# Power.net
KiCad netlist of a schematic drawn in Altium Designer
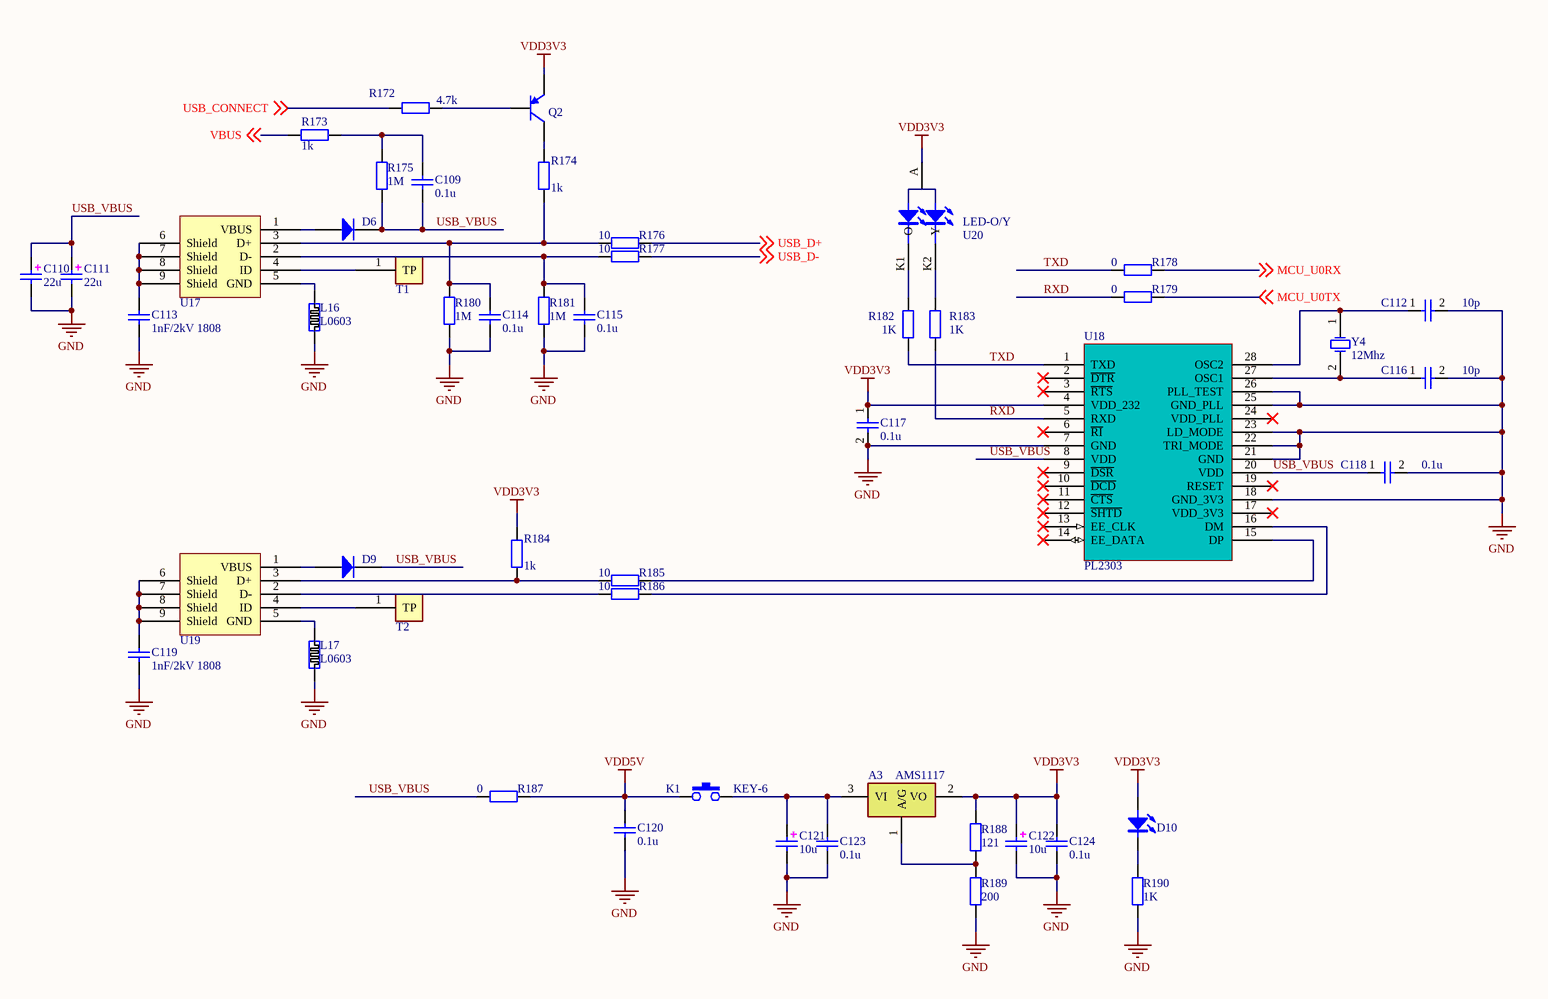
[diagram p0: Power.SchDoc]

(export (version "E")
  (design (tool "Eeschema 10.0.6"))
  (components
    (comp (ref "A3")
      (value "AMS1117")
      (footprint "ASM1117-A")
      (description "1117 LDO")
      (libsource (lib "lpc2368") (part "AMS1117"))
    )
    (comp (ref "C109")
      (value "0.1u")
      (footprint "C0603")
      (description "0603 Capacitor without Polarity")
      (libsource (lib "lpc2368") (part "CAP0603"))
    )
    (comp (ref "C110")
      (value "22u")
      (footprint "C1210")
      (description "钽电容1210封装")
      (libsource (lib "lpc2368") (part "DCAP"))
    )
    (comp (ref "C111")
      (value "22u")
      (footprint "C1210")
      (description "钽电容1210封装")
      (libsource (lib "lpc2368") (part "DCAP"))
    )
    (comp (ref "C112") (value "10p") (footprint "C0603") (libsource (lib "MSP430-LQFP64") (part "cap0603")))
    (comp (ref "C113")
      (value "1nF/2kV 1808")
      (footprint "C1808")
      (description "0603 Capacitor without Polarity")
      (libsource (lib "lpc2368") (part "CAP0603"))
    )
    (comp (ref "C114")
      (value "0.1u")
      (footprint "C0603")
      (description "0603 Capacitor without Polarity")
      (libsource (lib "lpc2368") (part "CAP0603"))
    )
    (comp (ref "C115")
      (value "0.1u")
      (footprint "C0603")
      (description "0603 Capacitor without Polarity")
      (libsource (lib "lpc2368") (part "CAP0603"))
    )
    (comp (ref "C116") (value "10p") (footprint "C0603") (libsource (lib "MSP430-LQFP64") (part "cap0603")))
    (comp (ref "C117") (value "0.1u") (footprint "C0603") (libsource (lib "MSP430-LQFP64") (part "cap0603")))
    (comp (ref "C118") (value "0.1u") (footprint "C0603") (libsource (lib "MSP430-LQFP64") (part "cap0603")))
    (comp (ref "C119")
      (value "1nF/2kV 1808")
      (footprint "C1808")
      (description "0603 Capacitor without Polarity")
      (libsource (lib "lpc2368") (part "CAP0603"))
    )
    (comp (ref "C120")
      (value "0.1u")
      (footprint "C0603")
      (description "0603 Capacitor without Polarity")
      (libsource (lib "lpc2368") (part "CAP0603"))
    )
    (comp (ref "C121")
      (value "10u")
      (footprint "C1210")
      (description "钽电容1210封装")
      (libsource (lib "lpc2368") (part "DCAP"))
    )
    (comp (ref "C122")
      (value "10u")
      (footprint "C1210")
      (description "钽电容1210封装")
      (libsource (lib "lpc2368") (part "DCAP"))
    )
    (comp (ref "C123")
      (value "0.1u")
      (footprint "C0603")
      (description "0603 Capacitor without Polarity")
      (libsource (lib "lpc2368") (part "CAP0603"))
    )
    (comp (ref "C124")
      (value "0.1u")
      (footprint "C0603")
      (description "0603 Capacitor without Polarity")
      (libsource (lib "lpc2368") (part "CAP0603"))
    )
    (comp (ref "D6")
      (value "D1N_SMT")
      (footprint "DIODE-SMT")
      (description "贴片二极管")
      (libsource (lib "lpc2368") (part "DIODE_SMT"))
    )
    (comp (ref "D9")
      (value "D1N_SMT")
      (footprint "DIODE-SMT")
      (description "贴片二极管")
      (libsource (lib "lpc2368") (part "DIODE_SMT"))
    )
    (comp (ref "D10")
      (value "LED_SMT")
      (footprint "LED0805")
      (description "贴片发光二极管")
      (libsource (lib "lpc2368") (part "LED_SMT"))
    )
    (comp (ref "K1")
      (value "KEY-6")
      (footprint "ZS-6")
      (description "自锁开关")
      (libsource (lib "MSP430-LQFP64") (part "KEY-6"))
    )
    (comp (ref "L16")
      (value "L0603")
      (footprint "L0603")
      (description "0603 Inductor")
      (libsource (lib "lpc2368") (part "L0603"))
    )
    (comp (ref "L17")
      (value "L0603")
      (footprint "L0603")
      (description "0603 Inductor")
      (libsource (lib "lpc2368") (part "L0603"))
    )
    (comp (ref "Q2")
      (value "PNP_SOT23")
      (footprint "T-SOT23")
      (description "PNP贴片封装,eg S8550")
      (libsource (lib "lpc2368") (part "PNP_SOT23"))
    )
    (comp (ref "R172")
      (value "4.7k")
      (footprint "R0603")
      (description "0603 Resistor")
      (libsource (lib "") (part "RES0603_3"))
    )
    (comp (ref "R173")
      (value "1k")
      (footprint "R0603")
      (description "0603 Resistor")
      (libsource (lib "") (part "RES0603_2"))
    )
    (comp (ref "R174")
      (value "1k")
      (footprint "R0603")
      (description "0603 Resistor")
      (libsource (lib "") (part "RES0603_1"))
    )
    (comp (ref "R175")
      (value "1M")
      (footprint "R0603")
      (description "0603 Resistor")
      (libsource (lib "") (part "RES0603_1"))
    )
    (comp (ref "R176")
      (value "10")
      (footprint "R0603")
      (description "0805 Resistor")
      (libsource (lib "lpc2368") (part "RES0805"))
    )
    (comp (ref "R177")
      (value "10")
      (footprint "R0603")
      (description "0805 Resistor")
      (libsource (lib "lpc2368") (part "RES0805"))
    )
    (comp (ref "R178")
      (value "0")
      (footprint "R0603")
      (description "0805 Resistor")
      (libsource (lib "lpc2368") (part "RES0805"))
    )
    (comp (ref "R179")
      (value "0")
      (footprint "R0603")
      (description "0805 Resistor")
      (libsource (lib "lpc2368") (part "RES0805"))
    )
    (comp (ref "R180")
      (value "1M")
      (footprint "R0603")
      (description "0603 Resistor")
      (libsource (lib "") (part "RES0603_1"))
    )
    (comp (ref "R181")
      (value "1M")
      (footprint "R0603")
      (description "0603 Resistor")
      (libsource (lib "") (part "RES0603_1"))
    )
    (comp (ref "R182")
      (value "1K")
      (footprint "R0603")
      (description "R06003")
      (libsource (lib "MSP430-LQFP64") (part "R06003"))
    )
    (comp (ref "R183")
      (value "1K")
      (footprint "R0603")
      (description "R06003")
      (libsource (lib "MSP430-LQFP64") (part "R06003"))
    )
    (comp (ref "R184")
      (value "1k")
      (footprint "R0603")
      (description "0603 Resistor")
      (libsource (lib "") (part "RES0603_1"))
    )
    (comp (ref "R185")
      (value "10")
      (footprint "R0603")
      (description "0805 Resistor")
      (libsource (lib "lpc2368") (part "RES0805"))
    )
    (comp (ref "R186")
      (value "10")
      (footprint "R0603")
      (description "0805 Resistor")
      (libsource (lib "lpc2368") (part "RES0805"))
    )
    (comp (ref "R187")
      (value "0")
      (footprint "R0603")
      (description "0805 Resistor")
      (libsource (lib "lpc2368") (part "RES0805"))
    )
    (comp (ref "R188")
      (value "121")
      (footprint "R0603")
      (description "0603 Resistor")
      (libsource (lib "lpc2368") (part "RES0603"))
    )
    (comp (ref "R189")
      (value "200")
      (footprint "R0603")
      (description "0603 Resistor")
      (libsource (lib "lpc2368") (part "RES0603"))
    )
    (comp (ref "R190")
      (value "1K")
      (footprint "R0603")
      (description "R06003")
      (libsource (lib "MSP430-LQFP64") (part "R06003"))
    )
    (comp (ref "T1")
      (value "TP")
      (footprint "TP30")
      (description "Test Point")
      (libsource (lib "lpc2368") (part "TP"))
    )
    (comp (ref "T2")
      (value "TP")
      (footprint "TP30")
      (description "Test Point")
      (libsource (lib "lpc2368") (part "TP"))
    )
    (comp (ref "U17")
      (value "USB_MINI_B")
      (footprint "USB_MINI_B")
      (description "mini USB")
      (libsource (lib "lpc2368") (part "USB_MINI_B"))
    )
    (comp (ref "U18") (value "PL2303") (footprint "SSOP28") (libsource (lib "MSP430-LQFP64") (part "PL2303")))
    (comp (ref "U19")
      (value "USB_MINI_B")
      (footprint "USB_MINI_B")
      (description "mini USB")
      (libsource (lib "lpc2368") (part "USB_MINI_B"))
    )
    (comp (ref "U20")
      (value "LED-O/Y")
      (footprint "LED3-I26-70")
      (libsource (lib "lpc2368") (part "LED-O/Y"))
    )
    (comp (ref "Y4")
      (value "12Mhz")
      (footprint "XTAL-SMD-LP")
      (description "2Pin晶振")
      (libsource (lib "MSP430-LQFP64") (part "XTAL"))
    )
  )
  (nets
    (net (code "1") (name "/RXD") (class "Default")
      (node (ref "R179") (pin "1") (pinfunction "1_1") (pintype "passive"))
      (node (ref "R183") (pin "2") (pinfunction "2_2") (pintype "passive"))
      (node (ref "U18") (pin "5") (pinfunction "RXD_5") (pintype "passive"))
    )
    (net (code "2") (name "/TXD") (class "Default")
      (node (ref "R178") (pin "1") (pinfunction "1_1") (pintype "passive"))
      (node (ref "R182") (pin "2") (pinfunction "2_2") (pintype "passive"))
      (node (ref "U18") (pin "1") (pinfunction "TXD_1") (pintype "passive"))
    )
    (net (code "3") (name "/USB_VBUS") (class "Default")
      (node (ref "C109") (pin "2") (pinfunction "2_2") (pintype "passive"))
      (node (ref "C110") (pin "1") (pinfunction "1_1") (pintype "passive"))
      (node (ref "C111") (pin "1") (pinfunction "1_1") (pintype "passive"))
      (node (ref "C118") (pin "1") (pinfunction "1_1") (pintype "passive"))
      (node (ref "D6") (pin "2") (pinfunction "2_2") (pintype "passive"))
      (node (ref "D9") (pin "2") (pinfunction "2_2") (pintype "passive"))
      (node (ref "R175") (pin "2") (pinfunction "2_2") (pintype "passive"))
      (node (ref "R187") (pin "1") (pinfunction "1_1") (pintype "passive"))
      (node (ref "U18") (pin "20") (pinfunction "VDD_20") (pintype "power_in"))
      (node (ref "U18") (pin "8") (pinfunction "VDD_8") (pintype "power_in"))
    )
    (net (code "4") (name "GND") (class "Default")
      (node (ref "C110") (pin "2") (pinfunction "2_2") (pintype "passive"))
      (node (ref "C111") (pin "2") (pinfunction "2_2") (pintype "passive"))
      (node (ref "C112") (pin "2") (pinfunction "2_2") (pintype "passive"))
      (node (ref "C113") (pin "1") (pinfunction "1_1") (pintype "passive"))
      (node (ref "C114") (pin "2") (pinfunction "2_2") (pintype "passive"))
      (node (ref "C115") (pin "2") (pinfunction "2_2") (pintype "passive"))
      (node (ref "C116") (pin "2") (pinfunction "2_2") (pintype "passive"))
      (node (ref "C117") (pin "2") (pinfunction "2_2") (pintype "passive"))
      (node (ref "C118") (pin "2") (pinfunction "2_2") (pintype "passive"))
      (node (ref "C119") (pin "1") (pinfunction "1_1") (pintype "passive"))
      (node (ref "C120") (pin "1") (pinfunction "1_1") (pintype "passive"))
      (node (ref "C121") (pin "2") (pinfunction "2_2") (pintype "passive"))
      (node (ref "C122") (pin "2") (pinfunction "2_2") (pintype "passive"))
      (node (ref "C123") (pin "1") (pinfunction "1_1") (pintype "passive"))
      (node (ref "C124") (pin "1") (pinfunction "1_1") (pintype "passive"))
      (node (ref "L16") (pin "1") (pinfunction "1_1") (pintype "passive"))
      (node (ref "L17") (pin "1") (pinfunction "1_1") (pintype "passive"))
      (node (ref "R180") (pin "2") (pinfunction "2_2") (pintype "passive"))
      (node (ref "R181") (pin "2") (pinfunction "2_2") (pintype "passive"))
      (node (ref "R189") (pin "1") (pinfunction "1_1") (pintype "passive"))
      (node (ref "R190") (pin "2") (pinfunction "2_2") (pintype "passive"))
      (node (ref "U18") (pin "18") (pinfunction "GND_3V3_18") (pintype "power_in"))
      (node (ref "U18") (pin "21") (pinfunction "GND_21") (pintype "power_in"))
      (node (ref "U18") (pin "22") (pinfunction "TRI_MODE_22") (pintype "passive"))
      (node (ref "U18") (pin "23") (pinfunction "LD_MODE_23") (pintype "passive"))
      (node (ref "U18") (pin "25") (pinfunction "GND_PLL_25") (pintype "power_in"))
      (node (ref "U18") (pin "26") (pinfunction "PLL_TEST_26") (pintype "passive"))
      (node (ref "U18") (pin "7") (pinfunction "GND_7") (pintype "power_in"))
    )
    (net (code "5") (name "MCU_U0RX") (class "Default")
      (node (ref "R178") (pin "2") (pinfunction "2_2") (pintype "passive"))
    )
    (net (code "6") (name "MCU_U0TX") (class "Default")
      (node (ref "R179") (pin "2") (pinfunction "2_2") (pintype "passive"))
    )
    (net (code "7") (name "Net-(A3-A{slash}G)") (class "Default")
      (node (ref "A3") (pin "1") (pinfunction "A/G_1") (pintype "passive"))
      (node (ref "R188") (pin "1") (pinfunction "1_1") (pintype "passive"))
      (node (ref "R189") (pin "2") (pinfunction "2_2") (pintype "passive"))
    )
    (net (code "8") (name "Net-(A3-VI)") (class "Default")
      (node (ref "A3") (pin "3") (pinfunction "VI_3") (pintype "passive"))
      (node (ref "C121") (pin "1") (pinfunction "1_1") (pintype "passive"))
      (node (ref "C123") (pin "2") (pinfunction "2_2") (pintype "passive"))
      (node (ref "K1") (pin "2") (pinfunction "2_2") (pintype "passive"))
    )
    (net (code "9") (name "Net-(C109-Pad1)") (class "Default")
      (node (ref "C109") (pin "1") (pinfunction "1_1") (pintype "passive"))
      (node (ref "R173") (pin "2") (pinfunction "2_2") (pintype "passive"))
      (node (ref "R175") (pin "1") (pinfunction "1_1") (pintype "passive"))
    )
    (net (code "10") (name "Net-(C113-Pad2)") (class "Default")
      (node (ref "C113") (pin "2") (pinfunction "2_2") (pintype "passive"))
      (node (ref "U17") (pin "6") (pinfunction "Shield_6") (pintype "passive"))
      (node (ref "U17") (pin "7") (pinfunction "Shield_7") (pintype "passive"))
      (node (ref "U17") (pin "8") (pinfunction "Shield_8") (pintype "passive"))
      (node (ref "U17") (pin "9") (pinfunction "Shield_9") (pintype "passive"))
    )
    (net (code "11") (name "Net-(C119-Pad2)") (class "Default")
      (node (ref "C119") (pin "2") (pinfunction "2_2") (pintype "passive"))
      (node (ref "U19") (pin "6") (pinfunction "Shield_6") (pintype "passive"))
      (node (ref "U19") (pin "7") (pinfunction "Shield_7") (pintype "passive"))
      (node (ref "U19") (pin "8") (pinfunction "Shield_8") (pintype "passive"))
      (node (ref "U19") (pin "9") (pinfunction "Shield_9") (pintype "passive"))
    )
    (net (code "12") (name "Net-(D10-PadK)") (class "Default")
      (node (ref "D10") (pin "K") (pinfunction "K_K") (pintype "passive"))
      (node (ref "R190") (pin "1") (pinfunction "1_1") (pintype "passive"))
    )
    (net (code "13") (name "Net-(Q2-B)") (class "Default")
      (node (ref "Q2") (pin "1") (pinfunction "B_1") (pintype "passive"))
      (node (ref "R172") (pin "1") (pinfunction "1_1") (pintype "passive"))
    )
    (net (code "14") (name "Net-(Q2-C)") (class "Default")
      (node (ref "Q2") (pin "3") (pinfunction "C_3") (pintype "passive"))
      (node (ref "R174") (pin "1") (pinfunction "1_1") (pintype "passive"))
    )
    (net (code "15") (name "Net-(T1-TP)") (class "Default")
      (node (ref "T1") (pin "1") (pinfunction "TP_1") (pintype "passive"))
      (node (ref "U17") (pin "4") (pinfunction "ID_4") (pintype "power_in"))
    )
    (net (code "16") (name "Net-(T2-TP)") (class "Default")
      (node (ref "T2") (pin "1") (pinfunction "TP_1") (pintype "passive"))
      (node (ref "U19") (pin "4") (pinfunction "ID_4") (pintype "power_in"))
    )
    (net (code "17") (name "Net-(U17-D+)") (class "Default")
      (node (ref "C114") (pin "1") (pinfunction "1_1") (pintype "passive"))
      (node (ref "R174") (pin "2") (pinfunction "2_2") (pintype "passive"))
      (node (ref "R176") (pin "1") (pinfunction "1_1") (pintype "passive"))
      (node (ref "R180") (pin "1") (pinfunction "1_1") (pintype "passive"))
      (node (ref "U17") (pin "3") (pinfunction "D+_3") (pintype "passive"))
    )
    (net (code "18") (name "Net-(U17-D-)") (class "Default")
      (node (ref "C115") (pin "1") (pinfunction "1_1") (pintype "passive"))
      (node (ref "R177") (pin "1") (pinfunction "1_1") (pintype "passive"))
      (node (ref "R181") (pin "1") (pinfunction "1_1") (pintype "passive"))
      (node (ref "U17") (pin "2") (pinfunction "D-_2") (pintype "passive"))
    )
    (net (code "19") (name "Net-(U17-GND)") (class "Default")
      (node (ref "L16") (pin "2") (pinfunction "2_2") (pintype "passive"))
      (node (ref "U17") (pin "5") (pinfunction "GND_5") (pintype "power_in"))
    )
    (net (code "20") (name "Net-(U17-VBUS)") (class "Default")
      (node (ref "D6") (pin "1") (pinfunction "1_1") (pintype "passive"))
      (node (ref "U17") (pin "1") (pinfunction "VBUS_1") (pintype "power_in"))
    )
    (net (code "21") (name "Net-(U18-DM)") (class "Default")
      (node (ref "R186") (pin "2") (pinfunction "2_2") (pintype "passive"))
      (node (ref "U18") (pin "16") (pinfunction "DM_16") (pintype "passive"))
    )
    (net (code "22") (name "Net-(U18-DP)") (class "Default")
      (node (ref "R185") (pin "2") (pinfunction "2_2") (pintype "passive"))
      (node (ref "U18") (pin "15") (pinfunction "DP_15") (pintype "passive"))
    )
    (net (code "23") (name "Net-(U18-OSC1)") (class "Default")
      (node (ref "C116") (pin "1") (pinfunction "1_1") (pintype "passive"))
      (node (ref "U18") (pin "27") (pinfunction "OSC1_27") (pintype "passive"))
      (node (ref "Y4") (pin "2") (pinfunction "OSC2_2") (pintype "passive"))
    )
    (net (code "24") (name "Net-(U18-OSC2)") (class "Default")
      (node (ref "C112") (pin "1") (pinfunction "1_1") (pintype "passive"))
      (node (ref "U18") (pin "28") (pinfunction "OSC2_28") (pintype "passive"))
      (node (ref "Y4") (pin "1") (pinfunction "OSC1_1") (pintype "passive"))
    )
    (net (code "25") (name "Net-(U19-D+)") (class "Default")
      (node (ref "R184") (pin "2") (pinfunction "2_2") (pintype "passive"))
      (node (ref "R185") (pin "1") (pinfunction "1_1") (pintype "passive"))
      (node (ref "U19") (pin "3") (pinfunction "D+_3") (pintype "passive"))
    )
    (net (code "26") (name "Net-(U19-D-)") (class "Default")
      (node (ref "R186") (pin "1") (pinfunction "1_1") (pintype "passive"))
      (node (ref "U19") (pin "2") (pinfunction "D-_2") (pintype "passive"))
    )
    (net (code "27") (name "Net-(U19-GND)") (class "Default")
      (node (ref "L17") (pin "2") (pinfunction "2_2") (pintype "passive"))
      (node (ref "U19") (pin "5") (pinfunction "GND_5") (pintype "power_in"))
    )
    (net (code "28") (name "Net-(U19-VBUS)") (class "Default")
      (node (ref "D9") (pin "1") (pinfunction "1_1") (pintype "passive"))
      (node (ref "U19") (pin "1") (pinfunction "VBUS_1") (pintype "power_in"))
    )
    (net (code "29") (name "Net-(U20-O)") (class "Default")
      (node (ref "R182") (pin "1") (pinfunction "1_1") (pintype "passive"))
      (node (ref "U20") (pin "K1") (pinfunction "O_K1") (pintype "passive"))
    )
    (net (code "30") (name "Net-(U20-Y)") (class "Default")
      (node (ref "R183") (pin "1") (pinfunction "1_1") (pintype "passive"))
      (node (ref "U20") (pin "K2") (pinfunction "Y_K2") (pintype "passive"))
    )
    (net (code "31") (name "USB_CONNECT") (class "Default")
      (node (ref "R172") (pin "2") (pinfunction "2_2") (pintype "passive"))
    )
    (net (code "32") (name "USB_D+") (class "Default")
      (node (ref "R176") (pin "2") (pinfunction "2_2") (pintype "passive"))
    )
    (net (code "33") (name "USB_D-") (class "Default")
      (node (ref "R177") (pin "2") (pinfunction "2_2") (pintype "passive"))
    )
    (net (code "34") (name "VBUS") (class "Default")
      (node (ref "R173") (pin "1") (pinfunction "1_1") (pintype "passive"))
    )
    (net (code "35") (name "VDD3V3") (class "Default")
      (node (ref "A3") (pin "2") (pinfunction "VO_2") (pintype "passive"))
      (node (ref "C117") (pin "1") (pinfunction "1_1") (pintype "passive"))
      (node (ref "C122") (pin "1") (pinfunction "1_1") (pintype "passive"))
      (node (ref "C124") (pin "2") (pinfunction "2_2") (pintype "passive"))
      (node (ref "D10") (pin "A") (pinfunction "A_A") (pintype "passive"))
      (node (ref "Q2") (pin "2") (pinfunction "E_2") (pintype "passive"))
      (node (ref "R184") (pin "1") (pinfunction "1_1") (pintype "passive"))
      (node (ref "R188") (pin "2") (pinfunction "2_2") (pintype "passive"))
      (node (ref "U18") (pin "4") (pinfunction "VDD_232_4") (pintype "power_in"))
      (node (ref "U20") (pin "A") (pinfunction "A_A") (pintype "passive"))
    )
    (net (code "36") (name "VDD5V") (class "Default")
      (node (ref "C120") (pin "2") (pinfunction "2_2") (pintype "passive"))
      (node (ref "K1") (pin "1") (pinfunction "1_1") (pintype "passive"))
      (node (ref "R187") (pin "2") (pinfunction "2_2") (pintype "passive"))
    )
    (net (code "37") (name "unconnected-(U18-EE_CLK-Pad13)") (class "Default")
      (node (ref "U18") (pin "13") (pinfunction "EE_CLK_13") (pintype "input+no_connect"))
    )
    (net (code "38") (name "unconnected-(U18-EE_DATA-Pad14)") (class "Default")
      (node (ref "U18") (pin "14") (pinfunction "EE_DATA_14") (pintype "bidirectional+no_connect"))
    )
    (net (code "39") (name "unconnected-(U18-RESET-Pad19)") (class "Default")
      (node (ref "U18") (pin "19") (pinfunction "RESET_19") (pintype "passive+no_connect"))
    )
    (net (code "40") (name "unconnected-(U18-VDD_3V3-Pad17)") (class "Default")
      (node (ref "U18") (pin "17") (pinfunction "VDD_3V3_17") (pintype "power_in+no_connect"))
    )
    (net (code "41") (name "unconnected-(U18-VDD_PLL-Pad24)") (class "Default")
      (node (ref "U18") (pin "24") (pinfunction "VDD_PLL_24") (pintype "power_in+no_connect"))
    )
    (net (code "42") (name "unconnected-(U18-~{CTS}-Pad11)") (class "Default")
      (node (ref "U18") (pin "11") (pinfunction "~{CTS}_11") (pintype "passive+no_connect"))
    )
    (net (code "43") (name "unconnected-(U18-~{DCD}-Pad10)") (class "Default")
      (node (ref "U18") (pin "10") (pinfunction "~{DCD}_10") (pintype "passive+no_connect"))
    )
    (net (code "44") (name "unconnected-(U18-~{DSR}-Pad9)") (class "Default")
      (node (ref "U18") (pin "9") (pinfunction "~{DSR}_9") (pintype "passive+no_connect"))
    )
    (net (code "45") (name "unconnected-(U18-~{DTR}-Pad2)") (class "Default")
      (node (ref "U18") (pin "2") (pinfunction "~{DTR}_2") (pintype "passive+no_connect"))
    )
    (net (code "46") (name "unconnected-(U18-~{RI}-Pad6)") (class "Default")
      (node (ref "U18") (pin "6") (pinfunction "~{RI}_6") (pintype "passive+no_connect"))
    )
    (net (code "47") (name "unconnected-(U18-~{RTS}-Pad3)") (class "Default")
      (node (ref "U18") (pin "3") (pinfunction "~{RTS}_3") (pintype "passive+no_connect"))
    )
    (net (code "48") (name "unconnected-(U18-~{SHTD}-Pad12)") (class "Default")
      (node (ref "U18") (pin "12") (pinfunction "~{SHTD}_12") (pintype "passive+no_connect"))
    )
  )
)
